# 03_power.net
KiCad netlist of a schematic drawn in Altium Designer
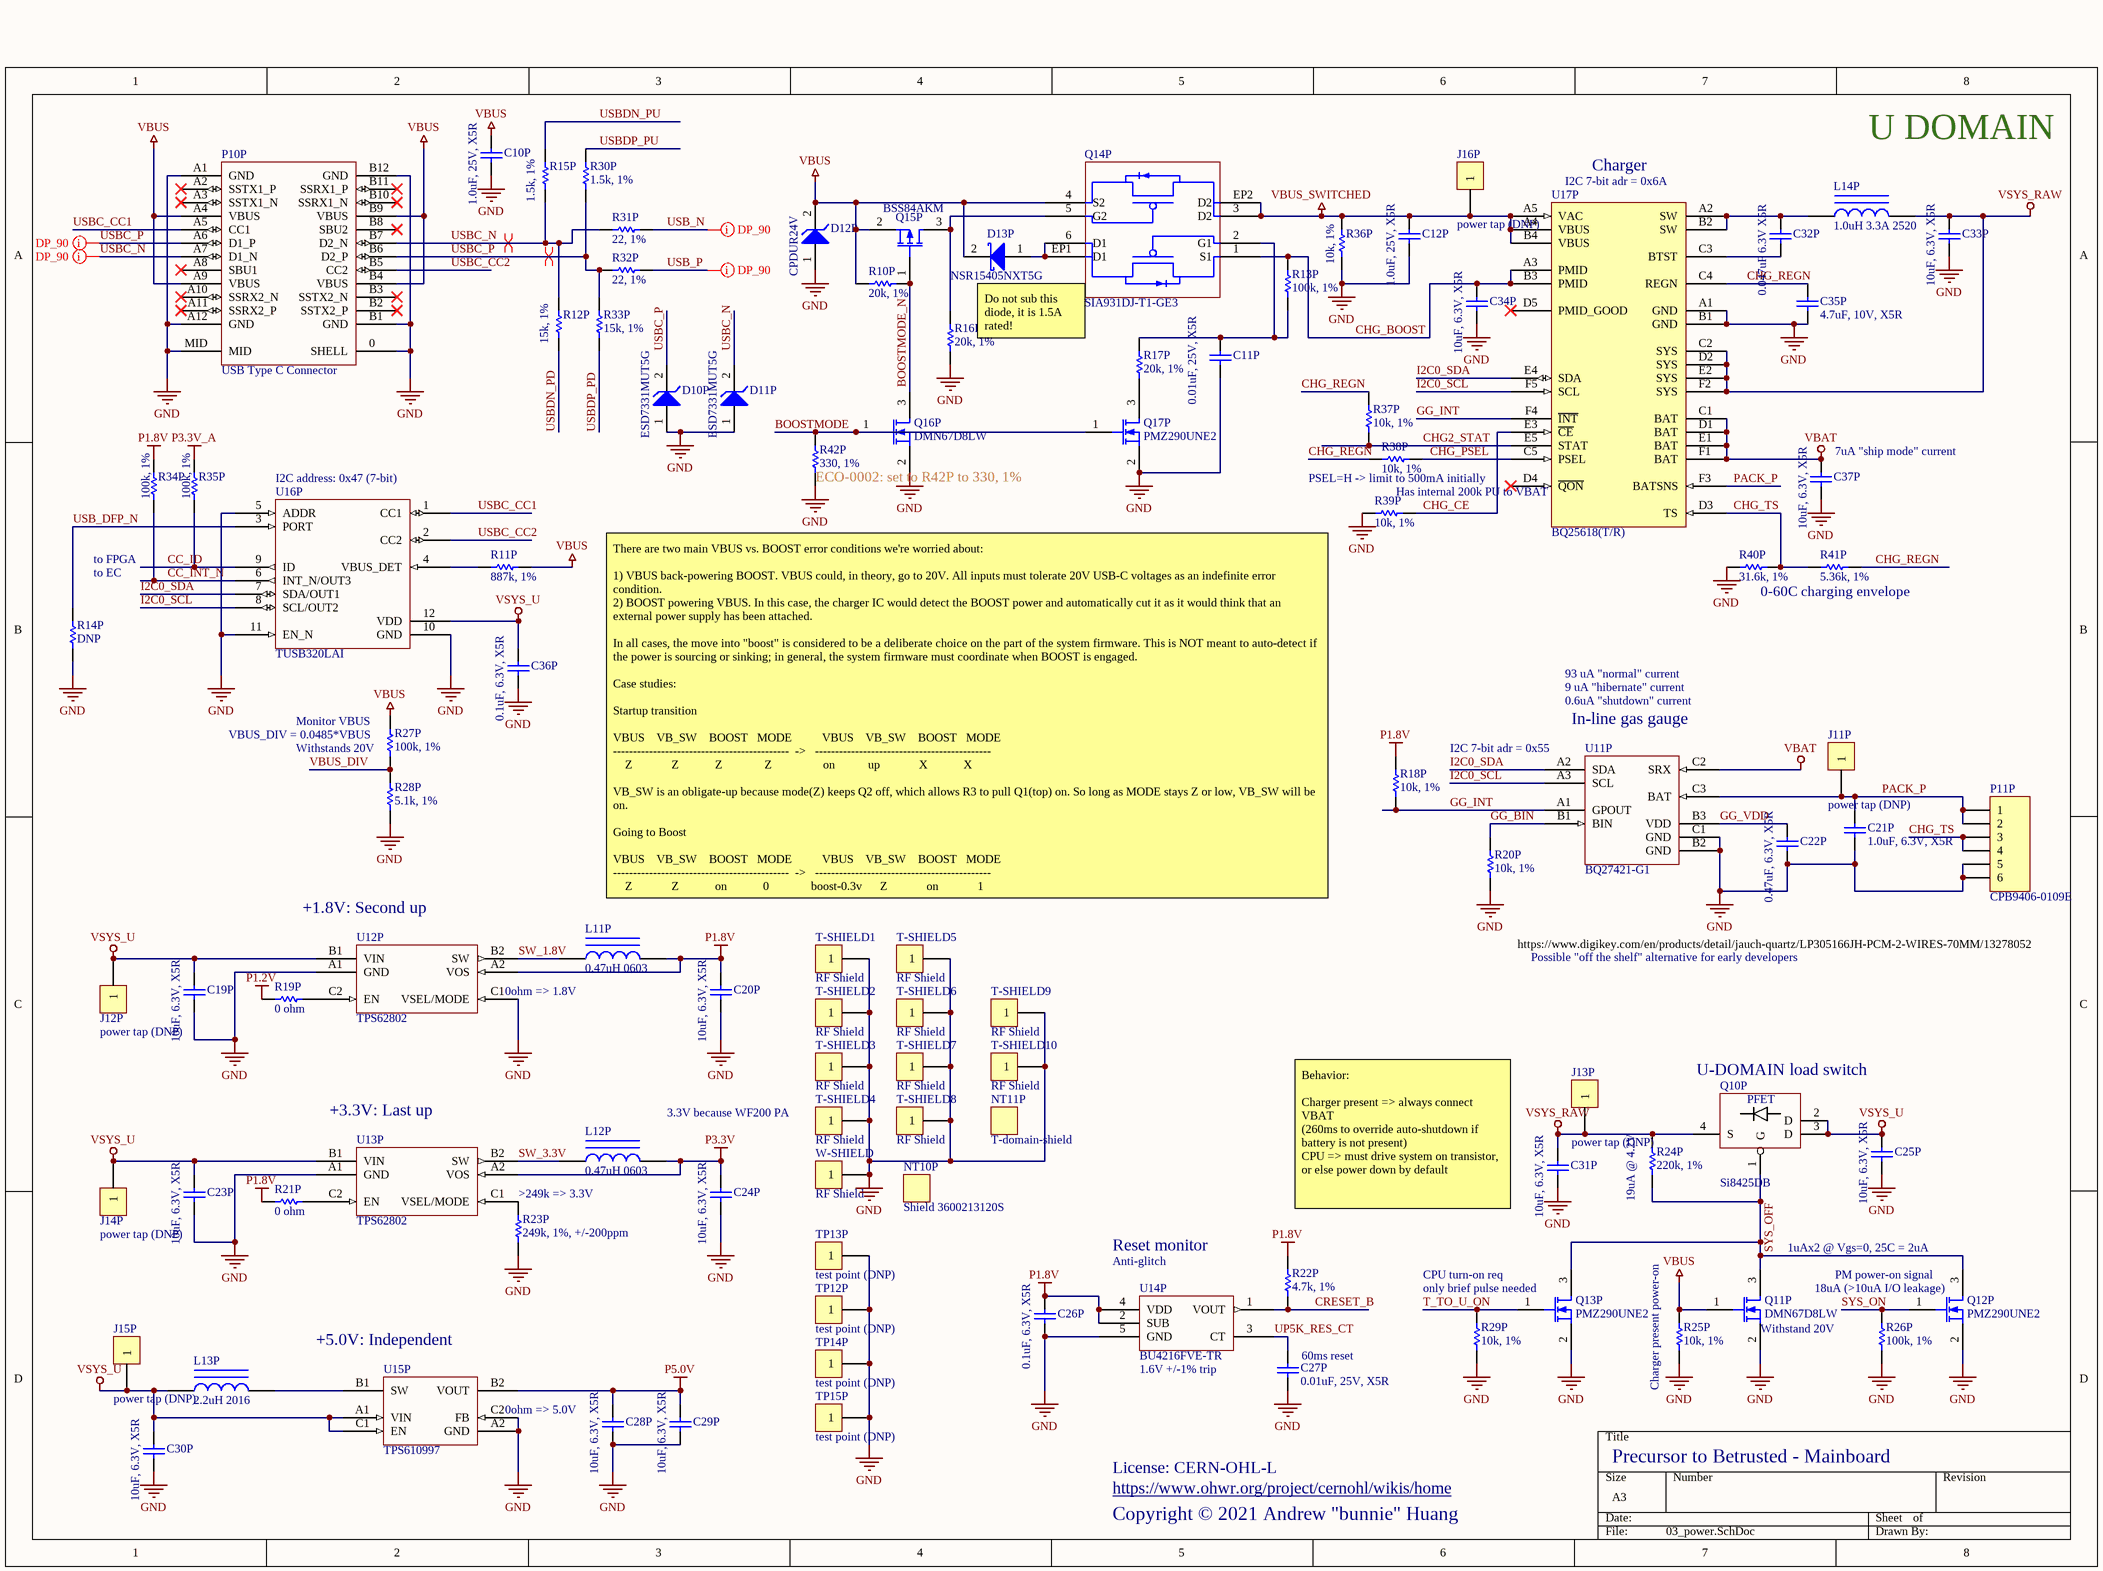
[diagram p0: 03_power.SchDoc]

(export (version "E")
  (design (tool "Eeschema 10.0.6"))
  (components
    (comp (ref "C10P")
      (value "1.0uF, 25V, X5R")
      (footprint "B_CAP0603")
      (description "Capacitor (Semiconductor SIM Model)")
      (fields (field (name "MPN") "CL10A105KA8NNNC"))
      (libsource (lib "Miscellaneous Devices") (part "Cap Semi"))
    )
    (comp (ref "C11P")
      (value "0.01uF, 25V, X5R")
      (footprint "B_RES0201")
      (description "Capacitor (Semiconductor SIM Model)")
      (fields (field (name "MPN") "GRM033R61E103KA12D"))
      (libsource (lib "Miscellaneous Devices") (part "Cap Semi"))
    )
    (comp (ref "C12P")
      (value "1.0uF, 25V, X5R")
      (footprint "B_CAP0603")
      (description "Capacitor (Semiconductor SIM Model)")
      (fields (field (name "MPN") "CL10A105KA8NNNC"))
      (libsource (lib "Miscellaneous Devices") (part "Cap Semi"))
    )
    (comp (ref "C19P")
      (value "10uF, 6.3V, X5R")
      (footprint "B_CAP0603")
      (description "Capacitor (Semiconductor SIM Model)")
      (fields (field (name "MPN") "CL10A106MQ8NNNC"))
      (libsource (lib "Miscellaneous Devices") (part "Cap Semi"))
    )
    (comp (ref "C20P")
      (value "10uF, 6.3V, X5R")
      (footprint "B_CAP0603")
      (description "Capacitor (Semiconductor SIM Model)")
      (fields (field (name "MPN") "CL10A106MQ8NNNC"))
      (libsource (lib "Miscellaneous Devices") (part "Cap Semi"))
    )
    (comp (ref "C21P")
      (value "1.0uF, 6.3V, X5R")
      (footprint "B_CAP0201")
      (description "Capacitor (Semiconductor SIM Model)")
      (fields (field (name "MPN") "GRM033R60J105MEA2D"))
      (libsource (lib "Miscellaneous Devices") (part "Cap Semi"))
    )
    (comp (ref "C22P")
      (value "0.47uF, 6.3V, X5R")
      (footprint "B_CAP0201")
      (description "Capacitor (Semiconductor SIM Model)")
      (fields (field (name "MPN") "CL03A474KQ3NNNH"))
      (libsource (lib "Miscellaneous Devices") (part "Cap Semi"))
    )
    (comp (ref "C23P")
      (value "10uF, 6.3V, X5R")
      (footprint "B_CAP0603")
      (description "Capacitor (Semiconductor SIM Model)")
      (fields (field (name "MPN") "CL10A106MQ8NNNC"))
      (libsource (lib "Miscellaneous Devices") (part "Cap Semi"))
    )
    (comp (ref "C24P")
      (value "10uF, 6.3V, X5R")
      (footprint "B_CAP0603")
      (description "Capacitor (Semiconductor SIM Model)")
      (fields (field (name "MPN") "CL10A106MQ8NNNC"))
      (libsource (lib "Miscellaneous Devices") (part "Cap Semi"))
    )
    (comp (ref "C25P")
      (value "10uF, 6.3V, X5R")
      (footprint "B_CAP0603")
      (description "Capacitor (Semiconductor SIM Model)")
      (fields (field (name "MPN") "CL10A106MQ8NNNC"))
      (libsource (lib "Miscellaneous Devices") (part "Cap Semi"))
    )
    (comp (ref "C26P")
      (value "0.1uF, 6.3V, X5R")
      (footprint "B_CAP0201")
      (description "Capacitor (Semiconductor SIM Model)")
      (fields (field (name "MPN") "CL03A104KQ3NNNC"))
      (libsource (lib "Miscellaneous Devices") (part "Cap Semi"))
    )
    (comp (ref "C27P")
      (value "0.01uF, 25V, X5R")
      (footprint "B_RES0201")
      (description "Capacitor (Semiconductor SIM Model)")
      (fields (field (name "MPN") "GRM033R61E103KA12D"))
      (libsource (lib "Miscellaneous Devices") (part "Cap Semi"))
    )
    (comp (ref "C28P")
      (value "10uF, 6.3V, X5R")
      (footprint "B_CAP0603")
      (description "Capacitor (Semiconductor SIM Model)")
      (fields (field (name "MPN") "CL10A106MQ8NNNC"))
      (libsource (lib "Miscellaneous Devices") (part "Cap Semi"))
    )
    (comp (ref "C29P")
      (value "10uF, 6.3V, X5R")
      (footprint "B_CAP0603")
      (description "Capacitor (Semiconductor SIM Model)")
      (fields (field (name "MPN") "CL10A106MQ8NNNC"))
      (libsource (lib "Miscellaneous Devices") (part "Cap Semi"))
    )
    (comp (ref "C30P")
      (value "10uF, 6.3V, X5R")
      (footprint "B_CAP0603")
      (description "Capacitor (Semiconductor SIM Model)")
      (fields (field (name "MPN") "CL10A106MQ8NNNC"))
      (libsource (lib "Miscellaneous Devices") (part "Cap Semi"))
    )
    (comp (ref "C31P")
      (value "10uF, 6.3V, X5R")
      (footprint "B_CAP0603")
      (description "Capacitor (Semiconductor SIM Model)")
      (fields (field (name "MPN") "CL10A106MQ8NNNC"))
      (libsource (lib "Miscellaneous Devices") (part "Cap Semi"))
    )
    (comp (ref "C32P")
      (value "0.047uF 6.3V X5R")
      (footprint "B_CAP0201")
      (description "Capacitor (Semiconductor SIM Model)")
      (fields (field (name "MPN") "GRM033C81A473KE05D"))
      (libsource (lib "Miscellaneous Devices") (part "Cap Semi"))
    )
    (comp (ref "C33P")
      (value "10uF, 6.3V, X5R")
      (footprint "B_CAP0603")
      (description "Capacitor (Semiconductor SIM Model)")
      (fields (field (name "MPN") "CL10A106MQ8NNNC"))
      (libsource (lib "Miscellaneous Devices") (part "Cap Semi"))
    )
    (comp (ref "C34P")
      (value "10uF, 6.3V, X5R")
      (footprint "B_CAP0603")
      (description "Capacitor (Semiconductor SIM Model)")
      (fields (field (name "MPN") "CL10A106MQ8NNNC"))
      (libsource (lib "Miscellaneous Devices") (part "Cap Semi"))
    )
    (comp (ref "C35P")
      (value "4.7uF, 10V, X5R")
      (footprint "B_CAP0603")
      (description "Capacitor (Semiconductor SIM Model)")
      (fields (field (name "MPN") "CL10A475KP8NNNC"))
      (libsource (lib "Miscellaneous Devices") (part "Cap Semi"))
    )
    (comp (ref "C36P")
      (value "0.1uF, 6.3V, X5R")
      (footprint "B_CAP0201")
      (description "Capacitor (Semiconductor SIM Model)")
      (fields (field (name "MPN") "CL03A104KQ3NNNC"))
      (libsource (lib "Miscellaneous Devices") (part "Cap Semi"))
    )
    (comp (ref "C37P")
      (value "10uF, 6.3V, X5R")
      (footprint "B_CAP0603")
      (description "Capacitor (Semiconductor SIM Model)")
      (fields (field (name "MPN") "CL10A106MQ8NNNC"))
      (libsource (lib "Miscellaneous Devices") (part "Cap Semi"))
    )
    (comp (ref "D10P")
      (value "ESD7331MUT5G")
      (footprint "D_X3DFN2_0201")
      (fields (field (name "PUBLISHER") "Altium Limited"))
      (libsource (lib "Miscellaneous Devices") (part "D Zener"))
    )
    (comp (ref "D11P")
      (value "ESD7331MUT5G")
      (footprint "D_X3DFN2_0201")
      (fields (field (name "PUBLISHER") "Altium Limited"))
      (libsource (lib "Miscellaneous Devices") (part "D Zener"))
    )
    (comp (ref "D12P")
      (value "CPDUR24V")
      (footprint "SOD523")
      (fields (field (name "PUBLISHER") "Altium Limited"))
      (libsource (lib "Miscellaneous Devices") (part "D Zener"))
    )
    (comp (ref "D13P")
      (value "NSR15405NXT5G")
      (footprint "B_DIO0502")
      (description "Schottky Rectifier")
      (libsource (lib "Miscellaneous Devices") (part "Diode 11DQ03"))
    )
    (comp (ref "J11P")
      (value "power tap (DNP)")
      (footprint "B_PWRTAP0402")
      (description "Connector")
      (fields (field (name "MPN") "DNP"))
      (libsource (lib "") (part "CON1_1"))
    )
    (comp (ref "J12P")
      (value "power tap (DNP)")
      (footprint "RESTAP-0603")
      (description "Connector")
      (fields (field (name "MPN") "DNP"))
      (libsource (lib "") (part "CON1_2"))
    )
    (comp (ref "J13P")
      (value "power tap (DNP)")
      (footprint "RESTAP-0603")
      (description "Connector")
      (fields (field (name "MPN") "DNP"))
      (libsource (lib "") (part "CON1_1"))
    )
    (comp (ref "J14P")
      (value "power tap (DNP)")
      (footprint "RESTAP-0603")
      (description "Connector")
      (fields (field (name "MPN") "DNP"))
      (libsource (lib "") (part "CON1_2"))
    )
    (comp (ref "J15P")
      (value "power tap (DNP)")
      (footprint "B_PWRTAP0402")
      (description "Connector")
      (fields (field (name "MPN") "DNP"))
      (libsource (lib "") (part "CON1_1"))
    )
    (comp (ref "J16P")
      (value "power tap (DNP)")
      (footprint "RESTAP-0603")
      (description "Connector")
      (fields (field (name "MPN") "DNP"))
      (libsource (lib "") (part "CON1_1"))
    )
    (comp (ref "L11P")
      (value "0.47uH 0603")
      (footprint "B_IND0603")
      (description "Magnetic-Core Inductor")
      (fields (field (name "MPN") "TFM160808ALC-R47MTAA"))
      (libsource (lib "Miscellaneous Devices") (part "Inductor Iron"))
    )
    (comp (ref "L12P")
      (value "0.47uH 0603")
      (footprint "B_IND0603")
      (description "Magnetic-Core Inductor")
      (fields (field (name "MPN") "TFM160808ALC-R47MTAA"))
      (libsource (lib "Miscellaneous Devices") (part "Inductor Iron"))
    )
    (comp (ref "L13P")
      (value "2.2uH 2016")
      (footprint "B_IND2016_TDK")
      (description "Magnetic-Core Inductor")
      (fields (field (name "MPN") "VLS201610CX-2R2M-1"))
      (libsource (lib "Miscellaneous Devices") (part "Inductor Iron"))
    )
    (comp (ref "L14P")
      (value "1.0uH 3.3A 2520")
      (footprint "B_IND2025_SAM")
      (description "Magnetic-Core Inductor")
      (fields (field (name "MPN") "CIGW252010GL1R0MNE"))
      (libsource (lib "Miscellaneous Devices") (part "Inductor Iron"))
    )
    (comp (ref "NT10P")
      (value "Shield 3600213120S")
      (description "RF Shield snap-on")
      (fields (field (name "MPN") "3600213120S"))
      (libsource (lib "commonsch") (part "NOTE"))
    )
    (comp (ref "NT11P")
      (value "T-domain-shield")
      (description "RF Shield snap-on C7521")
      (fields (field (name "MPN") "t-domain-shield-c7521"))
      (libsource (lib "commonsch") (part "NOTE"))
    )
    (comp (ref "P10P")
      (value "USB Type C Connector")
      (footprint "TE_1-2295018-2")
      (fields (field (name "MPN") "1-2295018-2"))
      (libsource (lib "commonsch-new") (part "USB_TYPE_C"))
    )
    (comp (ref "P11P")
      (value "CPB9406-0109E")
      (footprint "SMK_CPB9406-0109E")
      (description "Header, 6-Pin")
      (fields (field (name "PUBLISHER") "Altium Limited"))
      (libsource (lib "Miscellaneous Connectors") (part "Header 6"))
    )
    (comp (ref "Q10P")
      (value "Si8425DB")
      (footprint "VISHAY_MICRO_FOOT_4_BUMP")
      (description "P-channel 20V 6.2A 27mOhm @ -2.5V")
      (fields (field (name "MPN") "SI8425DB-T1-E1"))
      (libsource (lib "temp-to-merge") (part "Si8425DB"))
    )
    (comp (ref "Q11P")
      (value "DMN67D8LW")
      (footprint "SOT323-3AN")
      (description "N-Channel MOSFET")
      (fields (field (name "PUBLISHER") "Altium Limited"))
      (libsource (lib "Miscellaneous Devices") (part "MOSFET-N"))
    )
    (comp (ref "Q12P")
      (value "PMZ290UNE2")
      (footprint "SOT883")
      (description "N-Channel MOSFET")
      (fields (field (name "MPN") "PMZ290UNE2YL") (field (name "PUBLISHER") "Altium Limited"))
      (libsource (lib "Miscellaneous Devices") (part "MOSFET-N"))
    )
    (comp (ref "Q13P")
      (value "PMZ290UNE2")
      (footprint "SOT883")
      (description "N-Channel MOSFET")
      (fields (field (name "MPN") "PMZ290UNE2YL") (field (name "PUBLISHER") "Altium Limited"))
      (libsource (lib "Miscellaneous Devices") (part "MOSFET-N"))
    )
    (comp (ref "Q14P")
      (value "SIA931DJ-T1-GE3")
      (footprint "VISHAY_POWERPAK_SC70-6L")
      (description "Dual P-channel 30V MOSFET")
      (libsource (lib "commonsch-new") (part "SIA931DJ"))
    )
    (comp (ref "Q15P")
      (value "BSS84AKM")
      (footprint "SOT883")
      (description "P-Channel MOSFET")
      (fields (field (name "MPN") "BSS84AKM,315") (field (name "PUBLISHER") "Altium Limited"))
      (libsource (lib "Miscellaneous Devices") (part "MOSFET-P"))
    )
    (comp (ref "Q16P")
      (value "DMN67D8LW")
      (footprint "SOT323-3AN")
      (description "N-Channel MOSFET")
      (fields (field (name "PUBLISHER") "Altium Limited"))
      (libsource (lib "Miscellaneous Devices") (part "MOSFET-N"))
    )
    (comp (ref "Q17P")
      (value "PMZ290UNE2")
      (footprint "SOT883")
      (description "N-Channel MOSFET")
      (fields (field (name "MPN") "PMZ290UNE2YL") (field (name "PUBLISHER") "Altium Limited"))
      (libsource (lib "Miscellaneous Devices") (part "MOSFET-N"))
    )
    (comp (ref "R10P")
      (value "20k, 1%")
      (footprint "B_RES0201")
      (description "Resistor")
      (fields (field (name "MPN") "ANY"))
      (libsource (lib "Miscellaneous Devices") (part "Res1"))
    )
    (comp (ref "R11P")
      (value "887k, 1%")
      (footprint "B_RES0201")
      (description "Resistor")
      (fields (field (name "MPN") "ANY"))
      (libsource (lib "Miscellaneous Devices") (part "Res1"))
    )
    (comp (ref "R12P")
      (value "15k, 1%")
      (footprint "B_RES0201")
      (description "Resistor")
      (fields (field (name "MPN") "ANY"))
      (libsource (lib "Miscellaneous Devices") (part "Res1"))
    )
    (comp (ref "R13P")
      (value "100k, 1%")
      (footprint "B_RES0201")
      (description "Resistor")
      (fields (field (name "MPN") "ANY"))
      (libsource (lib "Miscellaneous Devices") (part "Res1"))
    )
    (comp (ref "R14P")
      (value "DNP")
      (footprint "B_RES0201")
      (description "Resistor")
      (fields (field (name "MPN") "ANY"))
      (libsource (lib "Miscellaneous Devices") (part "Res1"))
    )
    (comp (ref "R15P")
      (value "1.5k, 1%")
      (footprint "B_RES0201")
      (description "Resistor")
      (fields (field (name "MPN") "ANY"))
      (libsource (lib "Miscellaneous Devices") (part "Res1"))
    )
    (comp (ref "R16P")
      (value "20k, 1%")
      (footprint "B_RES0201")
      (description "Resistor")
      (fields (field (name "MPN") "ANY"))
      (libsource (lib "Miscellaneous Devices") (part "Res1"))
    )
    (comp (ref "R17P")
      (value "20k, 1%")
      (footprint "B_RES0201")
      (description "Resistor")
      (fields (field (name "MPN") "ANY"))
      (libsource (lib "Miscellaneous Devices") (part "Res1"))
    )
    (comp (ref "R18P")
      (value "10k, 1%")
      (footprint "B_RES0201")
      (description "Resistor")
      (fields (field (name "MPN") "ANY"))
      (libsource (lib "Miscellaneous Devices") (part "Res1"))
    )
    (comp (ref "R19P")
      (value "0 ohm")
      (footprint "B_RES0201")
      (description "Resistor")
      (fields (field (name "MPN") "ANY"))
      (libsource (lib "Miscellaneous Devices") (part "Res1"))
    )
    (comp (ref "R20P")
      (value "10k, 1%")
      (footprint "B_RES0201")
      (description "Resistor")
      (fields (field (name "MPN") "ANY"))
      (libsource (lib "Miscellaneous Devices") (part "Res1"))
    )
    (comp (ref "R21P")
      (value "0 ohm")
      (footprint "B_RES0201")
      (description "Resistor")
      (fields (field (name "MPN") "ANY"))
      (libsource (lib "Miscellaneous Devices") (part "Res1"))
    )
    (comp (ref "R22P")
      (value "4.7k, 1%")
      (footprint "B_RES0201")
      (description "Resistor")
      (fields (field (name "MPN") "ANY"))
      (libsource (lib "Miscellaneous Devices") (part "Res1"))
    )
    (comp (ref "R23P")
      (value "249k, 1%, +/-200ppm")
      (footprint "B_RES0402")
      (description "Resistor")
      (fields (field (name "MPN") "RC0402FR-07249KL"))
      (libsource (lib "Miscellaneous Devices") (part "Res1"))
    )
    (comp (ref "R24P")
      (value "220k, 1%")
      (footprint "B_RES0201")
      (description "Resistor")
      (fields (field (name "MPN") "ANY"))
      (libsource (lib "Miscellaneous Devices") (part "Res1"))
    )
    (comp (ref "R25P")
      (value "10k, 1%")
      (footprint "B_RES0201")
      (description "Resistor")
      (fields (field (name "MPN") "ANY"))
      (libsource (lib "Miscellaneous Devices") (part "Res1"))
    )
    (comp (ref "R26P")
      (value "100k, 1%")
      (footprint "B_RES0201")
      (description "Resistor")
      (fields (field (name "MPN") "ANY"))
      (libsource (lib "Miscellaneous Devices") (part "Res1"))
    )
    (comp (ref "R27P")
      (value "100k, 1%")
      (footprint "B_RES0201")
      (description "Resistor")
      (fields (field (name "MPN") "ANY"))
      (libsource (lib "Miscellaneous Devices") (part "Res1"))
    )
    (comp (ref "R28P")
      (value "5.1k, 1%")
      (footprint "B_RES0201")
      (description "Resistor")
      (fields (field (name "MPN") "ANY"))
      (libsource (lib "Miscellaneous Devices") (part "Res1"))
    )
    (comp (ref "R29P")
      (value "10k, 1%")
      (footprint "B_RES0201")
      (description "Resistor")
      (fields (field (name "MPN") "ANY"))
      (libsource (lib "Miscellaneous Devices") (part "Res1"))
    )
    (comp (ref "R30P")
      (value "1.5k, 1%")
      (footprint "B_RES0201")
      (description "Resistor")
      (fields (field (name "MPN") "ANY"))
      (libsource (lib "Miscellaneous Devices") (part "Res1"))
    )
    (comp (ref "R31P")
      (value "22, 1%")
      (footprint "B_RES0201")
      (description "Resistor")
      (fields (field (name "MPN") "ANY"))
      (libsource (lib "Miscellaneous Devices") (part "Res1"))
    )
    (comp (ref "R32P")
      (value "22, 1%")
      (footprint "B_RES0201")
      (description "Resistor")
      (fields (field (name "MPN") "ANY"))
      (libsource (lib "Miscellaneous Devices") (part "Res1"))
    )
    (comp (ref "R33P")
      (value "15k, 1%")
      (footprint "B_RES0201")
      (description "Resistor")
      (fields (field (name "MPN") "ANY"))
      (libsource (lib "Miscellaneous Devices") (part "Res1"))
    )
    (comp (ref "R34P")
      (value "100k, 1%")
      (footprint "B_RES0201")
      (description "Resistor")
      (fields (field (name "MPN") "ANY"))
      (libsource (lib "Miscellaneous Devices") (part "Res1"))
    )
    (comp (ref "R35P")
      (value "100k, 1%")
      (footprint "B_RES0201")
      (description "Resistor")
      (fields (field (name "MPN") "ANY"))
      (libsource (lib "Miscellaneous Devices") (part "Res1"))
    )
    (comp (ref "R36P")
      (value "10k, 1%")
      (footprint "B_RES0201")
      (description "Resistor")
      (fields (field (name "MPN") "ANY"))
      (libsource (lib "Miscellaneous Devices") (part "Res1"))
    )
    (comp (ref "R37P")
      (value "10k, 1%")
      (footprint "B_RES0201")
      (description "Resistor")
      (fields (field (name "MPN") "ANY"))
      (libsource (lib "Miscellaneous Devices") (part "Res1"))
    )
    (comp (ref "R38P")
      (value "10k, 1%")
      (footprint "B_RES0201")
      (description "Resistor")
      (fields (field (name "MPN") "ANY"))
      (libsource (lib "Miscellaneous Devices") (part "Res1"))
    )
    (comp (ref "R39P")
      (value "10k, 1%")
      (footprint "B_RES0201")
      (description "Resistor")
      (fields (field (name "MPN") "ANY"))
      (libsource (lib "Miscellaneous Devices") (part "Res1"))
    )
    (comp (ref "R40P")
      (value "31.6k, 1%")
      (footprint "B_RES0201")
      (description "Resistor")
      (fields (field (name "MPN") "ANY"))
      (libsource (lib "Miscellaneous Devices") (part "Res1"))
    )
    (comp (ref "R41P")
      (value "5.36k, 1%")
      (footprint "B_RES0201")
      (description "Resistor")
      (fields (field (name "MPN") "ANY"))
      (libsource (lib "Miscellaneous Devices") (part "Res1"))
    )
    (comp (ref "R42P")
      (value "330, 1%")
      (footprint "B_RES0201")
      (description "Resistor")
      (fields (field (name "MPN") "ANY"))
      (libsource (lib "Miscellaneous Devices") (part "Res1"))
    )
    (comp (ref "T-SHIELD1")
      (value "RF Shield")
      (footprint "WURTH_36900000")
      (description "Connector")
      (fields (field (name "MPN") "FDX0070A1"))
      (libsource (lib "*") (part "CON1"))
    )
    (comp (ref "T-SHIELD2")
      (value "RF Shield")
      (footprint "WURTH_36900000")
      (description "Connector")
      (fields (field (name "MPN") "FDX0070A1"))
      (libsource (lib "*") (part "CON1"))
    )
    (comp (ref "T-SHIELD3")
      (value "RF Shield")
      (footprint "WURTH_36900000")
      (description "Connector")
      (fields (field (name "MPN") "FDX0070A1"))
      (libsource (lib "*") (part "CON1"))
    )
    (comp (ref "T-SHIELD4")
      (value "RF Shield")
      (footprint "WURTH_36900000")
      (description "Connector")
      (fields (field (name "MPN") "FDX0070A1"))
      (libsource (lib "*") (part "CON1"))
    )
    (comp (ref "T-SHIELD5")
      (value "RF Shield")
      (footprint "WURTH_36900000")
      (description "Connector")
      (fields (field (name "MPN") "FDX0070A1"))
      (libsource (lib "*") (part "CON1"))
    )
    (comp (ref "T-SHIELD6")
      (value "RF Shield")
      (footprint "WURTH_36900000")
      (description "Connector")
      (fields (field (name "MPN") "FDX0070A1"))
      (libsource (lib "*") (part "CON1"))
    )
    (comp (ref "T-SHIELD7")
      (value "RF Shield")
      (footprint "WURTH_36900000")
      (description "Connector")
      (fields (field (name "MPN") "FDX0070A1"))
      (libsource (lib "*") (part "CON1"))
    )
    (comp (ref "T-SHIELD8")
      (value "RF Shield")
      (footprint "WURTH_36900000")
      (description "Connector")
      (fields (field (name "MPN") "FDX0070A1"))
      (libsource (lib "*") (part "CON1"))
    )
    (comp (ref "T-SHIELD9")
      (value "RF Shield")
      (footprint "WURTH_36900000")
      (description "Connector")
      (fields (field (name "MPN") "FDX0070A1"))
      (libsource (lib "*") (part "CON1"))
    )
    (comp (ref "T-SHIELD10")
      (value "RF Shield")
      (footprint "WURTH_36900000")
      (description "Connector")
      (fields (field (name "MPN") "FDX0070A1"))
      (libsource (lib "*") (part "CON1"))
    )
    (comp (ref "TP12P")
      (value "test point (DNP)")
      (footprint "TP_2MM_SQ")
      (description "Connector")
      (fields (field (name "MPN") "DNP"))
      (libsource (lib "*") (part "CON1"))
    )
    (comp (ref "TP13P")
      (value "test point (DNP)")
      (footprint "TP_2MM_SQ")
      (description "Connector")
      (fields (field (name "MPN") "DNP"))
      (libsource (lib "*") (part "CON1"))
    )
    (comp (ref "TP14P")
      (value "test point (DNP)")
      (footprint "TP_2MM_SQ")
      (description "Connector")
      (fields (field (name "MPN") "DNP"))
      (libsource (lib "*") (part "CON1"))
    )
    (comp (ref "TP15P")
      (value "test point (DNP)")
      (footprint "TP_2MM_SQ")
      (description "Connector")
      (fields (field (name "MPN") "DNP"))
      (libsource (lib "*") (part "CON1"))
    )
    (comp (ref "U11P")
      (value "BQ27421-G1")
      (footprint "BGA9C50P3X3_162X158X62")
      (description "System-Side Impedance Track Fuel Gauge with integrated Sense Resistor")
      (fields (field (name "MPN") "bq27421YZFT-G1A"))
      (libsource (lib "altium-import") (part "root_0_BQ27421-G1_"))
    )
    (comp (ref "U12P")
      (value "TPS62802")
      (footprint "BGA6C35P2X3_70X105X40_NSMD")
      (description "Buck regulator, 4MHz, 0.6A, 1.8V-3.3V, low Iq")
      (fields (field (name "MPN") "TPS62802YKAR"))
      (libsource (lib "altium-import") (part "root_0_TPS62802_"))
    )
    (comp (ref "U13P")
      (value "TPS62802")
      (footprint "BGA6C35P2X3_70X105X40_NSMD")
      (description "Buck regulator, 4MHz, 0.6A, 1.8V-3.3V, low Iq")
      (fields (field (name "MPN") "TPS62802YKAR"))
      (libsource (lib "altium-import") (part "root_0_TPS62802_"))
    )
    (comp (ref "U14P")
      (value "BU4216FVE-TR")
      (footprint "ROHM_VSOF5")
      (description "Low voltage free delay time setting CMOS voltage detector IC")
      (libsource (lib "commonsch-new") (part "BU42xxFVE"))
    )
    (comp (ref "U15P")
      (value "TPS610997")
      (footprint "BGA6C40P2X3_88X123X62")
      (description "Synchronous Boost Converter with Ultra-Low Iq")
      (fields (field (name "MPN") "TPS610997YFFR"))
      (libsource (lib "altium-import") (part "root_0_TPS610997_"))
    )
    (comp (ref "U16P")
      (value "TUSB320LAI")
      (footprint "QFN40P160X160X40-12N")
      (description "USB Type-C Configuration Channel Logic and Port Control")
      (fields (field (name "MPN") "TUSB320LAIRWBR"))
      (libsource (lib "commonsch-new") (part "TUSB320LAI"))
    )
    (comp (ref "U17P")
      (value "BQ25618(T/R)")
      (footprint "BGA30C40P5X6_196X236X62")
      (description "I2C controlled 1-cell 1.5A battery charger with 20mA termination and 1A boost operation")
      (fields (field (name "MPN") "BQ25618YFFT"))
      (libsource (lib "commonsch-new") (part "BQ25618"))
    )
    (comp (ref "W-SHIELD")
      (value "RF Shield")
      (footprint "WURTH_36X021312XS")
      (description "Connector")
      (fields (field (name "MPN") "3610213126S"))
      (libsource (lib "*") (part "CON1"))
    )
  )
  (nets
    (net (code "1") (name "/BOOSTMODE") (class "Default")
      (node (ref "Q16P") (pin "1") (pinfunction "G_1") (pintype "passive"))
      (node (ref "Q17P") (pin "1") (pinfunction "G_1") (pintype "passive"))
      (node (ref "R42P") (pin "2") (pinfunction "2_2") (pintype "passive"))
    )
    (net (code "2") (name "/BOOSTMODE_N") (class "Default")
      (node (ref "Q15P") (pin "1") (pinfunction "G_1") (pintype "passive"))
      (node (ref "Q16P") (pin "3") (pinfunction "D_3") (pintype "passive"))
      (node (ref "R10P") (pin "1") (pinfunction "1_1") (pintype "passive"))
    )
    (net (code "3") (name "/CC_ID") (class "Default")
      (node (ref "R35P") (pin "1") (pinfunction "1_1") (pintype "passive"))
      (node (ref "U16P") (pin "9") (pinfunction "ID_9") (pintype "output"))
    )
    (net (code "4") (name "/CC_INT_N") (class "Default")
      (node (ref "R34P") (pin "1") (pinfunction "1_1") (pintype "passive"))
      (node (ref "U16P") (pin "6") (pinfunction "INT_N/OUT3_6") (pintype "output"))
    )
    (net (code "5") (name "/CHG2_STAT") (class "Default")
      (node (ref "R37P") (pin "2") (pinfunction "2_2") (pintype "passive"))
      (node (ref "U17P") (pin "E5") (pinfunction "STAT_E5") (pintype "open_collector"))
    )
    (net (code "6") (name "/CHG_BOOST") (class "Default")
      (node (ref "C34P") (pin "1") (pinfunction "1_1") (pintype "passive"))
      (node (ref "Q14P") (pin "1") (pinfunction "S1_1") (pintype "passive"))
      (node (ref "R13P") (pin "1") (pinfunction "1_1") (pintype "passive"))
      (node (ref "U17P") (pin "A3") (pinfunction "PMID_A3") (pintype "power_in"))
      (node (ref "U17P") (pin "B3") (pinfunction "PMID_B3") (pintype "power_in"))
    )
    (net (code "7") (name "/CHG_CE") (class "Default")
      (node (ref "R39P") (pin "2") (pinfunction "2_2") (pintype "passive"))
      (node (ref "U17P") (pin "E3") (pinfunction "~{CE}_E3") (pintype "input"))
    )
    (net (code "8") (name "/CHG_PSEL") (class "Default")
      (node (ref "R38P") (pin "2") (pinfunction "2_2") (pintype "passive"))
      (node (ref "U17P") (pin "C5") (pinfunction "PSEL_C5") (pintype "input"))
    )
    (net (code "9") (name "/CHG_REGN") (class "Default")
      (node (ref "C35P") (pin "2") (pinfunction "2_2") (pintype "passive"))
      (node (ref "R37P") (pin "1") (pinfunction "1_1") (pintype "passive"))
      (node (ref "R38P") (pin "1") (pinfunction "1_1") (pintype "passive"))
      (node (ref "R41P") (pin "2") (pinfunction "2_2") (pintype "passive"))
      (node (ref "U17P") (pin "C4") (pinfunction "REGN_C4") (pintype "power_in"))
    )
    (net (code "10") (name "/CHG_TS") (class "Default")
      (node (ref "P11P") (pin "3") (pinfunction "3_3") (pintype "passive"))
      (node (ref "P11P") (pin "4") (pinfunction "4_4") (pintype "passive"))
      (node (ref "R40P") (pin "2") (pinfunction "2_2") (pintype "passive"))
      (node (ref "R41P") (pin "1") (pinfunction "1_1") (pintype "passive"))
      (node (ref "U17P") (pin "D3") (pinfunction "TS_D3") (pintype "input"))
    )
    (net (code "11") (name "/CRESET_B") (class "Default")
      (node (ref "R22P") (pin "1") (pinfunction "1_1") (pintype "passive"))
      (node (ref "U14P") (pin "1") (pinfunction "VOUT_1") (pintype "output"))
    )
    (net (code "12") (name "/GG_BIN") (class "Default")
      (node (ref "R20P") (pin "1") (pinfunction "1_1") (pintype "passive"))
      (node (ref "U11P") (pin "B1") (pinfunction "BIN_B1") (pintype "input"))
    )
    (net (code "13") (name "/GG_INT") (class "Default")
      (node (ref "R18P") (pin "2") (pinfunction "2_2") (pintype "passive"))
      (node (ref "U11P") (pin "A1") (pinfunction "GPOUT_A1") (pintype "open_collector"))
      (node (ref "U17P") (pin "F4") (pinfunction "~{INT}_F4") (pintype "open_collector"))
    )
    (net (code "14") (name "/GG_VDD") (class "Default")
      (node (ref "C22P") (pin "1") (pinfunction "1_1") (pintype "passive"))
      (node (ref "U11P") (pin "B3") (pinfunction "VDD_B3") (pintype "power_in"))
    )
    (net (code "15") (name "/I2C0_SCL") (class "Default")
      (node (ref "U11P") (pin "A3") (pinfunction "SCL_A3") (pintype "open_collector"))
      (node (ref "U16P") (pin "8") (pinfunction "SCL/OUT2_8") (pintype "bidirectional"))
      (node (ref "U17P") (pin "F5") (pinfunction "SCL_F5") (pintype "input"))
    )
    (net (code "16") (name "/I2C0_SDA") (class "Default")
      (node (ref "U11P") (pin "A2") (pinfunction "SDA_A2") (pintype "open_collector"))
      (node (ref "U16P") (pin "7") (pinfunction "SDA/OUT1_7") (pintype "bidirectional"))
      (node (ref "U17P") (pin "E4") (pinfunction "SDA_E4") (pintype "bidirectional"))
    )
    (net (code "17") (name "/PACK_P") (class "Default")
      (node (ref "C21P") (pin "2") (pinfunction "2_2") (pintype "passive"))
      (node (ref "J11P") (pin "1") (pinfunction "1_1") (pintype "passive"))
      (node (ref "P11P") (pin "1") (pinfunction "1_1") (pintype "passive"))
      (node (ref "P11P") (pin "2") (pinfunction "2_2") (pintype "passive"))
      (node (ref "U11P") (pin "C3") (pinfunction "BAT_C3") (pintype "input"))
      (node (ref "U17P") (pin "F3") (pinfunction "BATSNS_F3") (pintype "input"))
    )
    (net (code "18") (name "/SW_1.8V") (class "Default")
      (node (ref "L11P") (pin "1") (pinfunction "1_1") (pintype "passive"))
      (node (ref "U12P") (pin "B2") (pinfunction "SW_B2") (pintype "output"))
    )
    (net (code "19") (name "/SW_3.3V") (class "Default")
      (node (ref "L12P") (pin "1") (pinfunction "1_1") (pintype "passive"))
      (node (ref "U13P") (pin "B2") (pinfunction "SW_B2") (pintype "output"))
    )
    (net (code "20") (name "/SYS_OFF") (class "Default")
      (node (ref "Q10P") (pin "1") (pinfunction "G_1") (pintype "passive"))
      (node (ref "Q11P") (pin "3") (pinfunction "D_3") (pintype "passive"))
      (node (ref "Q12P") (pin "3") (pinfunction "D_3") (pintype "passive"))
      (node (ref "Q13P") (pin "3") (pinfunction "D_3") (pintype "passive"))
      (node (ref "R24P") (pin "1") (pinfunction "1_1") (pintype "passive"))
    )
    (net (code "21") (name "/SYS_ON") (class "Default")
      (node (ref "Q12P") (pin "1") (pinfunction "G_1") (pintype "passive"))
      (node (ref "R26P") (pin "2") (pinfunction "2_2") (pintype "passive"))
    )
    (net (code "22") (name "/T_TO_U_ON") (class "Default")
      (node (ref "Q13P") (pin "1") (pinfunction "G_1") (pintype "passive"))
      (node (ref "R29P") (pin "1") (pinfunction "1_1") (pintype "passive"))
    )
    (net (code "23") (name "/UP5K_RES_CT") (class "Default")
      (node (ref "C27P") (pin "1") (pinfunction "1_1") (pintype "passive"))
      (node (ref "U14P") (pin "3") (pinfunction "CT_3") (pintype "passive"))
    )
    (net (code "24") (name "/USBC_CC1") (class "Default")
      (node (ref "P10P") (pin "A5") (pinfunction "CC1_A5") (pintype "bidirectional"))
      (node (ref "U16P") (pin "1") (pinfunction "CC1_1") (pintype "bidirectional"))
    )
    (net (code "25") (name "/USBC_CC2") (class "Default")
      (node (ref "P10P") (pin "B5") (pinfunction "CC2_B5") (pintype "bidirectional"))
      (node (ref "U16P") (pin "2") (pinfunction "CC2_2") (pintype "bidirectional"))
    )
    (net (code "26") (name "/USBC_N") (class "Default")
      (node (ref "D11P") (pin "2") (pinfunction "K_2") (pintype "passive"))
      (node (ref "P10P") (pin "A7") (pinfunction "D1_N_A7") (pintype "bidirectional"))
      (node (ref "P10P") (pin "B7") (pinfunction "D2_N_B7") (pintype "bidirectional"))
      (node (ref "R12P") (pin "1") (pinfunction "1_1") (pintype "passive"))
      (node (ref "R15P") (pin "1") (pinfunction "1_1") (pintype "passive"))
      (node (ref "R31P") (pin "1") (pinfunction "1_1") (pintype "passive"))
    )
    (net (code "27") (name "/USBC_P") (class "Default")
      (node (ref "D10P") (pin "2") (pinfunction "K_2") (pintype "passive"))
      (node (ref "P10P") (pin "A6") (pinfunction "D1_P_A6") (pintype "bidirectional"))
      (node (ref "P10P") (pin "B6") (pinfunction "D2_P_B6") (pintype "bidirectional"))
      (node (ref "R30P") (pin "1") (pinfunction "1_1") (pintype "passive"))
      (node (ref "R32P") (pin "1") (pinfunction "1_1") (pintype "passive"))
      (node (ref "R33P") (pin "1") (pinfunction "1_1") (pintype "passive"))
    )
    (net (code "28") (name "/USBDN_PD") (class "Default")
      (node (ref "R12P") (pin "2") (pinfunction "2_2") (pintype "passive"))
    )
    (net (code "29") (name "/USBDN_PU") (class "Default")
      (node (ref "R15P") (pin "2") (pinfunction "2_2") (pintype "passive"))
    )
    (net (code "30") (name "/USBDP_PD") (class "Default")
      (node (ref "R33P") (pin "2") (pinfunction "2_2") (pintype "passive"))
    )
    (net (code "31") (name "/USBDP_PU") (class "Default")
      (node (ref "R30P") (pin "2") (pinfunction "2_2") (pintype "passive"))
    )
    (net (code "32") (name "/USB_DFP_N") (class "Default")
      (node (ref "R14P") (pin "1") (pinfunction "1_1") (pintype "passive"))
      (node (ref "U16P") (pin "3") (pinfunction "PORT_3") (pintype "input"))
    )
    (net (code "33") (name "/USB_N") (class "Default")
      (node (ref "R31P") (pin "2") (pinfunction "2_2") (pintype "passive"))
    )
    (net (code "34") (name "/USB_P") (class "Default")
      (node (ref "R32P") (pin "2") (pinfunction "2_2") (pintype "passive"))
    )
    (net (code "35") (name "/VBUS_DIV") (class "Default")
      (node (ref "R27P") (pin "1") (pinfunction "1_1") (pintype "passive"))
      (node (ref "R28P") (pin "1") (pinfunction "1_1") (pintype "passive"))
    )
    (net (code "36") (name "GND") (class "Default")
      (node (ref "C10P") (pin "2") (pinfunction "2_2") (pintype "passive"))
      (node (ref "C11P") (pin "2") (pinfunction "2_2") (pintype "passive"))
      (node (ref "C12P") (pin "2") (pinfunction "2_2") (pintype "passive"))
      (node (ref "C19P") (pin "2") (pinfunction "2_2") (pintype "passive"))
      (node (ref "C20P") (pin "2") (pinfunction "2_2") (pintype "passive"))
      (node (ref "C21P") (pin "1") (pinfunction "1_1") (pintype "passive"))
      (node (ref "C22P") (pin "2") (pinfunction "2_2") (pintype "passive"))
      (node (ref "C23P") (pin "2") (pinfunction "2_2") (pintype "passive"))
      (node (ref "C24P") (pin "2") (pinfunction "2_2") (pintype "passive"))
      (node (ref "C25P") (pin "2") (pinfunction "2_2") (pintype "passive"))
      (node (ref "C26P") (pin "2") (pinfunction "2_2") (pintype "passive"))
      (node (ref "C27P") (pin "2") (pinfunction "2_2") (pintype "passive"))
      (node (ref "C28P") (pin "2") (pinfunction "2_2") (pintype "passive"))
      (node (ref "C29P") (pin "2") (pinfunction "2_2") (pintype "passive"))
      (node (ref "C30P") (pin "2") (pinfunction "2_2") (pintype "passive"))
      (node (ref "C31P") (pin "2") (pinfunction "2_2") (pintype "passive"))
      (node (ref "C33P") (pin "2") (pinfunction "2_2") (pintype "passive"))
      (node (ref "C34P") (pin "2") (pinfunction "2_2") (pintype "passive"))
      (node (ref "C35P") (pin "1") (pinfunction "1_1") (pintype "passive"))
      (node (ref "C36P") (pin "2") (pinfunction "2_2") (pintype "passive"))
      (node (ref "C37P") (pin "2") (pinfunction "2_2") (pintype "passive"))
      (node (ref "D10P") (pin "1") (pinfunction "A_1") (pintype "passive"))
      (node (ref "D11P") (pin "1") (pinfunction "A_1") (pintype "passive"))
      (node (ref "D12P") (pin "1") (pinfunction "A_1") (pintype "passive"))
      (node (ref "P10P") (pin "0") (pinfunction "SHELL_0") (pintype "passive"))
      (node (ref "P10P") (pin "A1") (pinfunction "GND_A1") (pintype "power_in"))
      (node (ref "P10P") (pin "A12") (pinfunction "GND_A12") (pintype "power_in"))
      (node (ref "P10P") (pin "B1") (pinfunction "GND_B1") (pintype "power_in"))
      (node (ref "P10P") (pin "B12") (pinfunction "GND_B12") (pintype "power_in"))
      (node (ref "P10P") (pin "MID") (pinfunction "MID_MID") (pintype "passive"))
      (node (ref "P11P") (pin "5") (pinfunction "5_5") (pintype "passive"))
      (node (ref "P11P") (pin "6") (pinfunction "6_6") (pintype "passive"))
      (node (ref "Q11P") (pin "2") (pinfunction "S_2") (pintype "passive"))
      (node (ref "Q12P") (pin "2") (pinfunction "S_2") (pintype "passive"))
      (node (ref "Q13P") (pin "2") (pinfunction "S_2") (pintype "passive"))
      (node (ref "Q16P") (pin "2") (pinfunction "S_2") (pintype "passive"))
      (node (ref "Q17P") (pin "2") (pinfunction "S_2") (pintype "passive"))
      (node (ref "R14P") (pin "2") (pinfunction "2_2") (pintype "passive"))
      (node (ref "R16P") (pin "1") (pinfunction "1_1") (pintype "passive"))
      (node (ref "R20P") (pin "2") (pinfunction "2_2") (pintype "passive"))
      (node (ref "R23P") (pin "2") (pinfunction "2_2") (pintype "passive"))
      (node (ref "R25P") (pin "2") (pinfunction "2_2") (pintype "passive"))
      (node (ref "R26P") (pin "1") (pinfunction "1_1") (pintype "passive"))
      (node (ref "R28P") (pin "2") (pinfunction "2_2") (pintype "passive"))
      (node (ref "R29P") (pin "2") (pinfunction "2_2") (pintype "passive"))
      (node (ref "R36P") (pin "1") (pinfunction "1_1") (pintype "passive"))
      (node (ref "R39P") (pin "1") (pinfunction "1_1") (pintype "passive"))
      (node (ref "R40P") (pin "1") (pinfunction "1_1") (pintype "passive"))
      (node (ref "R42P") (pin "1") (pinfunction "1_1") (pintype "passive"))
      (node (ref "T-SHIELD1") (pin "1") (pinfunction "1_1") (pintype "passive"))
      (node (ref "T-SHIELD10") (pin "1") (pinfunction "1_1") (pintype "passive"))
      (node (ref "T-SHIELD2") (pin "1") (pinfunction "1_1") (pintype "passive"))
      (node (ref "T-SHIELD3") (pin "1") (pinfunction "1_1") (pintype "passive"))
      (node (ref "T-SHIELD4") (pin "1") (pinfunction "1_1") (pintype "passive"))
      (node (ref "T-SHIELD5") (pin "1") (pinfunction "1_1") (pintype "passive"))
      (node (ref "T-SHIELD6") (pin "1") (pinfunction "1_1") (pintype "passive"))
      (node (ref "T-SHIELD7") (pin "1") (pinfunction "1_1") (pintype "passive"))
      (node (ref "T-SHIELD8") (pin "1") (pinfunction "1_1") (pintype "passive"))
      (node (ref "T-SHIELD9") (pin "1") (pinfunction "1_1") (pintype "passive"))
      (node (ref "TP12P") (pin "1") (pinfunction "1_1") (pintype "passive"))
      (node (ref "TP13P") (pin "1") (pinfunction "1_1") (pintype "passive"))
      (node (ref "TP14P") (pin "1") (pinfunction "1_1") (pintype "passive"))
      (node (ref "TP15P") (pin "1") (pinfunction "1_1") (pintype "passive"))
      (node (ref "U11P") (pin "B2") (pinfunction "GND_B2") (pintype "power_in"))
      (node (ref "U11P") (pin "C1") (pinfunction "GND_C1") (pintype "power_in"))
      (node (ref "U12P") (pin "A1") (pinfunction "GND_A1") (pintype "power_in"))
      (node (ref "U12P") (pin "C1") (pinfunction "VSEL/MODE_C1") (pintype "input"))
      (node (ref "U13P") (pin "A1") (pinfunction "GND_A1") (pintype "power_in"))
      (node (ref "U14P") (pin "5") (pinfunction "GND_5") (pintype "power_in"))
      (node (ref "U15P") (pin "A2") (pinfunction "GND_A2") (pintype "power_in"))
      (node (ref "U15P") (pin "C2") (pinfunction "FB_C2") (pintype "input"))
      (node (ref "U16P") (pin "10") (pinfunction "GND_10") (pintype "power_in"))
      (node (ref "U16P") (pin "11") (pinfunction "EN_N_11") (pintype "input"))
      (node (ref "U16P") (pin "5") (pinfunction "ADDR_5") (pintype "input"))
      (node (ref "U17P") (pin "A1") (pinfunction "GND_A1") (pintype "power_in"))
      (node (ref "U17P") (pin "B1") (pinfunction "GND_B1") (pintype "power_in"))
      (node (ref "W-SHIELD") (pin "1") (pinfunction "1_1") (pintype "passive"))
    )
    (net (code "37") (name "Net-(C32P-Pad1)") (class "Default")
      (node (ref "C32P") (pin "1") (pinfunction "1_1") (pintype "passive"))
      (node (ref "L14P") (pin "1") (pinfunction "1_1") (pintype "passive"))
      (node (ref "U17P") (pin "A2") (pinfunction "SW_A2") (pintype "power_in"))
      (node (ref "U17P") (pin "B2") (pinfunction "SW_B2") (pintype "power_in"))
    )
    (net (code "38") (name "Net-(D13P-A)") (class "Default")
      (node (ref "D13P") (pin "1") (pinfunction "A_1") (pintype "passive"))
      (node (ref "Q14P") (pin "6") (pinfunction "D1_6") (pintype "passive"))
      (node (ref "Q14P") (pin "EP1") (pinfunction "D1_EP1") (pintype "passive"))
    )
    (net (code "39") (name "Net-(Q14P-G1)") (class "Default")
      (node (ref "C11P") (pin "1") (pinfunction "1_1") (pintype "passive"))
      (node (ref "Q14P") (pin "2") (pinfunction "G1_2") (pintype "passive"))
      (node (ref "R13P") (pin "2") (pinfunction "2_2") (pintype "passive"))
      (node (ref "R17P") (pin "2") (pinfunction "2_2") (pintype "passive"))
    )
    (net (code "40") (name "Net-(Q14P-G2)") (class "Default")
      (node (ref "Q14P") (pin "5") (pinfunction "G2_5") (pintype "passive"))
      (node (ref "Q15P") (pin "3") (pinfunction "D_3") (pintype "passive"))
      (node (ref "R16P") (pin "2") (pinfunction "2_2") (pintype "passive"))
    )
    (net (code "41") (name "Net-(Q17P-D)") (class "Default")
      (node (ref "Q17P") (pin "3") (pinfunction "D_3") (pintype "passive"))
      (node (ref "R17P") (pin "1") (pinfunction "1_1") (pintype "passive"))
    )
    (net (code "42") (name "Net-(U12P-EN)") (class "Default")
      (node (ref "R19P") (pin "2") (pinfunction "2_2") (pintype "passive"))
      (node (ref "U12P") (pin "C2") (pinfunction "EN_C2") (pintype "input"))
    )
    (net (code "43") (name "Net-(U13P-EN)") (class "Default")
      (node (ref "R21P") (pin "2") (pinfunction "2_2") (pintype "passive"))
      (node (ref "U13P") (pin "C2") (pinfunction "EN_C2") (pintype "input"))
    )
    (net (code "44") (name "Net-(U13P-VSEL{slash}MODE)") (class "Default")
      (node (ref "R23P") (pin "1") (pinfunction "1_1") (pintype "passive"))
      (node (ref "U13P") (pin "C1") (pinfunction "VSEL/MODE_C1") (pintype "input"))
    )
    (net (code "45") (name "Net-(U15P-SW)") (class "Default")
      (node (ref "L13P") (pin "2") (pinfunction "2_2") (pintype "passive"))
      (node (ref "U15P") (pin "B1") (pinfunction "SW_B1") (pintype "power_in"))
    )
    (net (code "46") (name "Net-(U16P-VBUS_DET)") (class "Default")
      (node (ref "R11P") (pin "2") (pinfunction "2_2") (pintype "passive"))
      (node (ref "U16P") (pin "4") (pinfunction "VBUS_DET_4") (pintype "input"))
    )
    (net (code "47") (name "Net-(U17P-BTST)") (class "Default")
      (node (ref "C32P") (pin "2") (pinfunction "2_2") (pintype "passive"))
      (node (ref "U17P") (pin "C3") (pinfunction "BTST_C3") (pintype "power_in"))
    )
    (net (code "48") (name "P1.2V") (class "Default")
      (node (ref "R19P") (pin "1") (pinfunction "1_1") (pintype "passive"))
    )
    (net (code "49") (name "P1.8V") (class "Default")
      (node (ref "C20P") (pin "1") (pinfunction "1_1") (pintype "passive"))
      (node (ref "C26P") (pin "1") (pinfunction "1_1") (pintype "passive"))
      (node (ref "L11P") (pin "2") (pinfunction "2_2") (pintype "passive"))
      (node (ref "R18P") (pin "1") (pinfunction "1_1") (pintype "passive"))
      (node (ref "R21P") (pin "1") (pinfunction "1_1") (pintype "passive"))
      (node (ref "R22P") (pin "2") (pinfunction "2_2") (pintype "passive"))
      (node (ref "R34P") (pin "2") (pinfunction "2_2") (pintype "passive"))
      (node (ref "U12P") (pin "A2") (pinfunction "VOS_A2") (pintype "input"))
      (node (ref "U14P") (pin "2") (pinfunction "SUB_2") (pintype "power_in"))
      (node (ref "U14P") (pin "4") (pinfunction "VDD_4") (pintype "power_in"))
    )
    (net (code "50") (name "P3.3V") (class "Default")
      (node (ref "C24P") (pin "1") (pinfunction "1_1") (pintype "passive"))
      (node (ref "L12P") (pin "2") (pinfunction "2_2") (pintype "passive"))
      (node (ref "U13P") (pin "A2") (pinfunction "VOS_A2") (pintype "input"))
    )
    (net (code "51") (name "P3.3V_A") (class "Default")
      (node (ref "R35P") (pin "2") (pinfunction "2_2") (pintype "passive"))
    )
    (net (code "52") (name "P5.0V") (class "Default")
      (node (ref "C28P") (pin "1") (pinfunction "1_1") (pintype "passive"))
      (node (ref "C29P") (pin "1") (pinfunction "1_1") (pintype "passive"))
      (node (ref "U15P") (pin "B2") (pinfunction "VOUT_B2") (pintype "power_in"))
    )
    (net (code "53") (name "VBAT") (class "Default")
      (node (ref "C37P") (pin "1") (pinfunction "1_1") (pintype "passive"))
      (node (ref "U11P") (pin "C2") (pinfunction "SRX_C2") (pintype "input"))
      (node (ref "U17P") (pin "C1") (pinfunction "BAT_C1") (pintype "power_in"))
      (node (ref "U17P") (pin "D1") (pinfunction "BAT_D1") (pintype "power_in"))
      (node (ref "U17P") (pin "E1") (pinfunction "BAT_E1") (pintype "power_in"))
      (node (ref "U17P") (pin "F1") (pinfunction "BAT_F1") (pintype "power_in"))
    )
    (net (code "54") (name "VBUS") (class "Default")
      (node (ref "C10P") (pin "1") (pinfunction "1_1") (pintype "passive"))
      (node (ref "D12P") (pin "2") (pinfunction "K_2") (pintype "passive"))
      (node (ref "D13P") (pin "2") (pinfunction "K_2") (pintype "passive"))
      (node (ref "P10P") (pin "A4") (pinfunction "VBUS_A4") (pintype "power_in"))
      (node (ref "P10P") (pin "A9") (pinfunction "VBUS_A9") (pintype "power_in"))
      (node (ref "P10P") (pin "B4") (pinfunction "VBUS_B4") (pintype "power_in"))
      (node (ref "P10P") (pin "B9") (pinfunction "VBUS_B9") (pintype "power_in"))
      (node (ref "Q11P") (pin "1") (pinfunction "G_1") (pintype "passive"))
      (node (ref "Q14P") (pin "4") (pinfunction "S2_4") (pintype "passive"))
      (node (ref "Q15P") (pin "2") (pinfunction "S_2") (pintype "passive"))
      (node (ref "R10P") (pin "2") (pinfunction "2_2") (pintype "passive"))
      (node (ref "R11P") (pin "1") (pinfunction "1_1") (pintype "passive"))
      (node (ref "R25P") (pin "1") (pinfunction "1_1") (pintype "passive"))
      (node (ref "R27P") (pin "2") (pinfunction "2_2") (pintype "passive"))
    )
    (net (code "55") (name "VBUS_SWITCHED") (class "Default")
      (node (ref "C12P") (pin "1") (pinfunction "1_1") (pintype "passive"))
      (node (ref "J16P") (pin "1") (pinfunction "1_1") (pintype "passive"))
      (node (ref "Q14P") (pin "3") (pinfunction "D2_3") (pintype "passive"))
      (node (ref "Q14P") (pin "EP2") (pinfunction "D2_EP2") (pintype "passive"))
      (node (ref "R36P") (pin "2") (pinfunction "2_2") (pintype "passive"))
      (node (ref "U17P") (pin "A4") (pinfunction "VBUS_A4") (pintype "power_in"))
      (node (ref "U17P") (pin "A5") (pinfunction "VAC_A5") (pintype "input"))
      (node (ref "U17P") (pin "B4") (pinfunction "VBUS_B4") (pintype "power_in"))
    )
    (net (code "56") (name "VSYS_RAW") (class "Default")
      (node (ref "C31P") (pin "1") (pinfunction "1_1") (pintype "passive"))
      (node (ref "C33P") (pin "1") (pinfunction "1_1") (pintype "passive"))
      (node (ref "J13P") (pin "1") (pinfunction "1_1") (pintype "passive"))
      (node (ref "L14P") (pin "2") (pinfunction "2_2") (pintype "passive"))
      (node (ref "Q10P") (pin "4") (pinfunction "S_4") (pintype "passive"))
      (node (ref "R24P") (pin "2") (pinfunction "2_2") (pintype "passive"))
      (node (ref "U17P") (pin "C2") (pinfunction "SYS_C2") (pintype "power_in"))
      (node (ref "U17P") (pin "D2") (pinfunction "SYS_D2") (pintype "power_in"))
      (node (ref "U17P") (pin "E2") (pinfunction "SYS_E2") (pintype "power_in"))
      (node (ref "U17P") (pin "F2") (pinfunction "SYS_F2") (pintype "power_in"))
    )
    (net (code "57") (name "VSYS_U") (class "Default")
      (node (ref "C19P") (pin "1") (pinfunction "1_1") (pintype "passive"))
      (node (ref "C23P") (pin "1") (pinfunction "1_1") (pintype "passive"))
      (node (ref "C25P") (pin "1") (pinfunction "1_1") (pintype "passive"))
      (node (ref "C30P") (pin "1") (pinfunction "1_1") (pintype "passive"))
      (node (ref "C36P") (pin "1") (pinfunction "1_1") (pintype "passive"))
      (node (ref "J12P") (pin "1") (pinfunction "1_1") (pintype "passive"))
      (node (ref "J14P") (pin "1") (pinfunction "1_1") (pintype "passive"))
      (node (ref "J15P") (pin "1") (pinfunction "1_1") (pintype "passive"))
      (node (ref "L13P") (pin "1") (pinfunction "1_1") (pintype "passive"))
      (node (ref "Q10P") (pin "2") (pinfunction "D_2") (pintype "passive"))
      (node (ref "Q10P") (pin "3") (pinfunction "D_3") (pintype "passive"))
      (node (ref "U12P") (pin "B1") (pinfunction "VIN_B1") (pintype "power_in"))
      (node (ref "U13P") (pin "B1") (pinfunction "VIN_B1") (pintype "power_in"))
      (node (ref "U15P") (pin "A1") (pinfunction "VIN_A1") (pintype "input"))
      (node (ref "U15P") (pin "C1") (pinfunction "EN_C1") (pintype "input"))
      (node (ref "U16P") (pin "12") (pinfunction "VDD_12") (pintype "power_in"))
    )
    (net (code "58") (name "unconnected-(P10P-SBU1-PadA8)") (class "Default")
      (node (ref "P10P") (pin "A8") (pinfunction "SBU1_A8") (pintype "passive+no_connect"))
    )
    (net (code "59") (name "unconnected-(P10P-SBU2-PadB8)") (class "Default")
      (node (ref "P10P") (pin "B8") (pinfunction "SBU2_B8") (pintype "passive+no_connect"))
    )
    (net (code "60") (name "unconnected-(P10P-SSRX1_N-PadB10)") (class "Default")
      (node (ref "P10P") (pin "B10") (pinfunction "SSRX1_N_B10") (pintype "bidirectional+no_connect"))
    )
    (net (code "61") (name "unconnected-(P10P-SSRX1_P-PadB11)") (class "Default")
      (node (ref "P10P") (pin "B11") (pinfunction "SSRX1_P_B11") (pintype "bidirectional+no_connect"))
    )
    (net (code "62") (name "unconnected-(P10P-SSRX2_N-PadA10)") (class "Default")
      (node (ref "P10P") (pin "A10") (pinfunction "SSRX2_N_A10") (pintype "bidirectional+no_connect"))
    )
    (net (code "63") (name "unconnected-(P10P-SSRX2_P-PadA11)") (class "Default")
      (node (ref "P10P") (pin "A11") (pinfunction "SSRX2_P_A11") (pintype "bidirectional+no_connect"))
    )
    (net (code "64") (name "unconnected-(P10P-SSTX1_N-PadA3)") (class "Default")
      (node (ref "P10P") (pin "A3") (pinfunction "SSTX1_N_A3") (pintype "bidirectional+no_connect"))
    )
    (net (code "65") (name "unconnected-(P10P-SSTX1_P-PadA2)") (class "Default")
      (node (ref "P10P") (pin "A2") (pinfunction "SSTX1_P_A2") (pintype "bidirectional+no_connect"))
    )
    (net (code "66") (name "unconnected-(P10P-SSTX2_N-PadB3)") (class "Default")
      (node (ref "P10P") (pin "B3") (pinfunction "SSTX2_N_B3") (pintype "power_in+no_connect"))
    )
    (net (code "67") (name "unconnected-(P10P-SSTX2_P-PadB2)") (class "Default")
      (node (ref "P10P") (pin "B2") (pinfunction "SSTX2_P_B2") (pintype "power_in+no_connect"))
    )
    (net (code "68") (name "unconnected-(U17P-PMID_GOOD-PadD5)") (class "Default")
      (node (ref "U17P") (pin "D5") (pinfunction "PMID_GOOD_D5") (pintype "open_collector+no_connect"))
    )
    (net (code "69") (name "unconnected-(U17P-~{QON}-PadD4)") (class "Default")
      (node (ref "U17P") (pin "D4") (pinfunction "~{QON}_D4") (pintype "input+no_connect"))
    )
  )
)
